# ESP32_ADC_DAC.net
KiCad netlist of a schematic drawn in Altium Designer
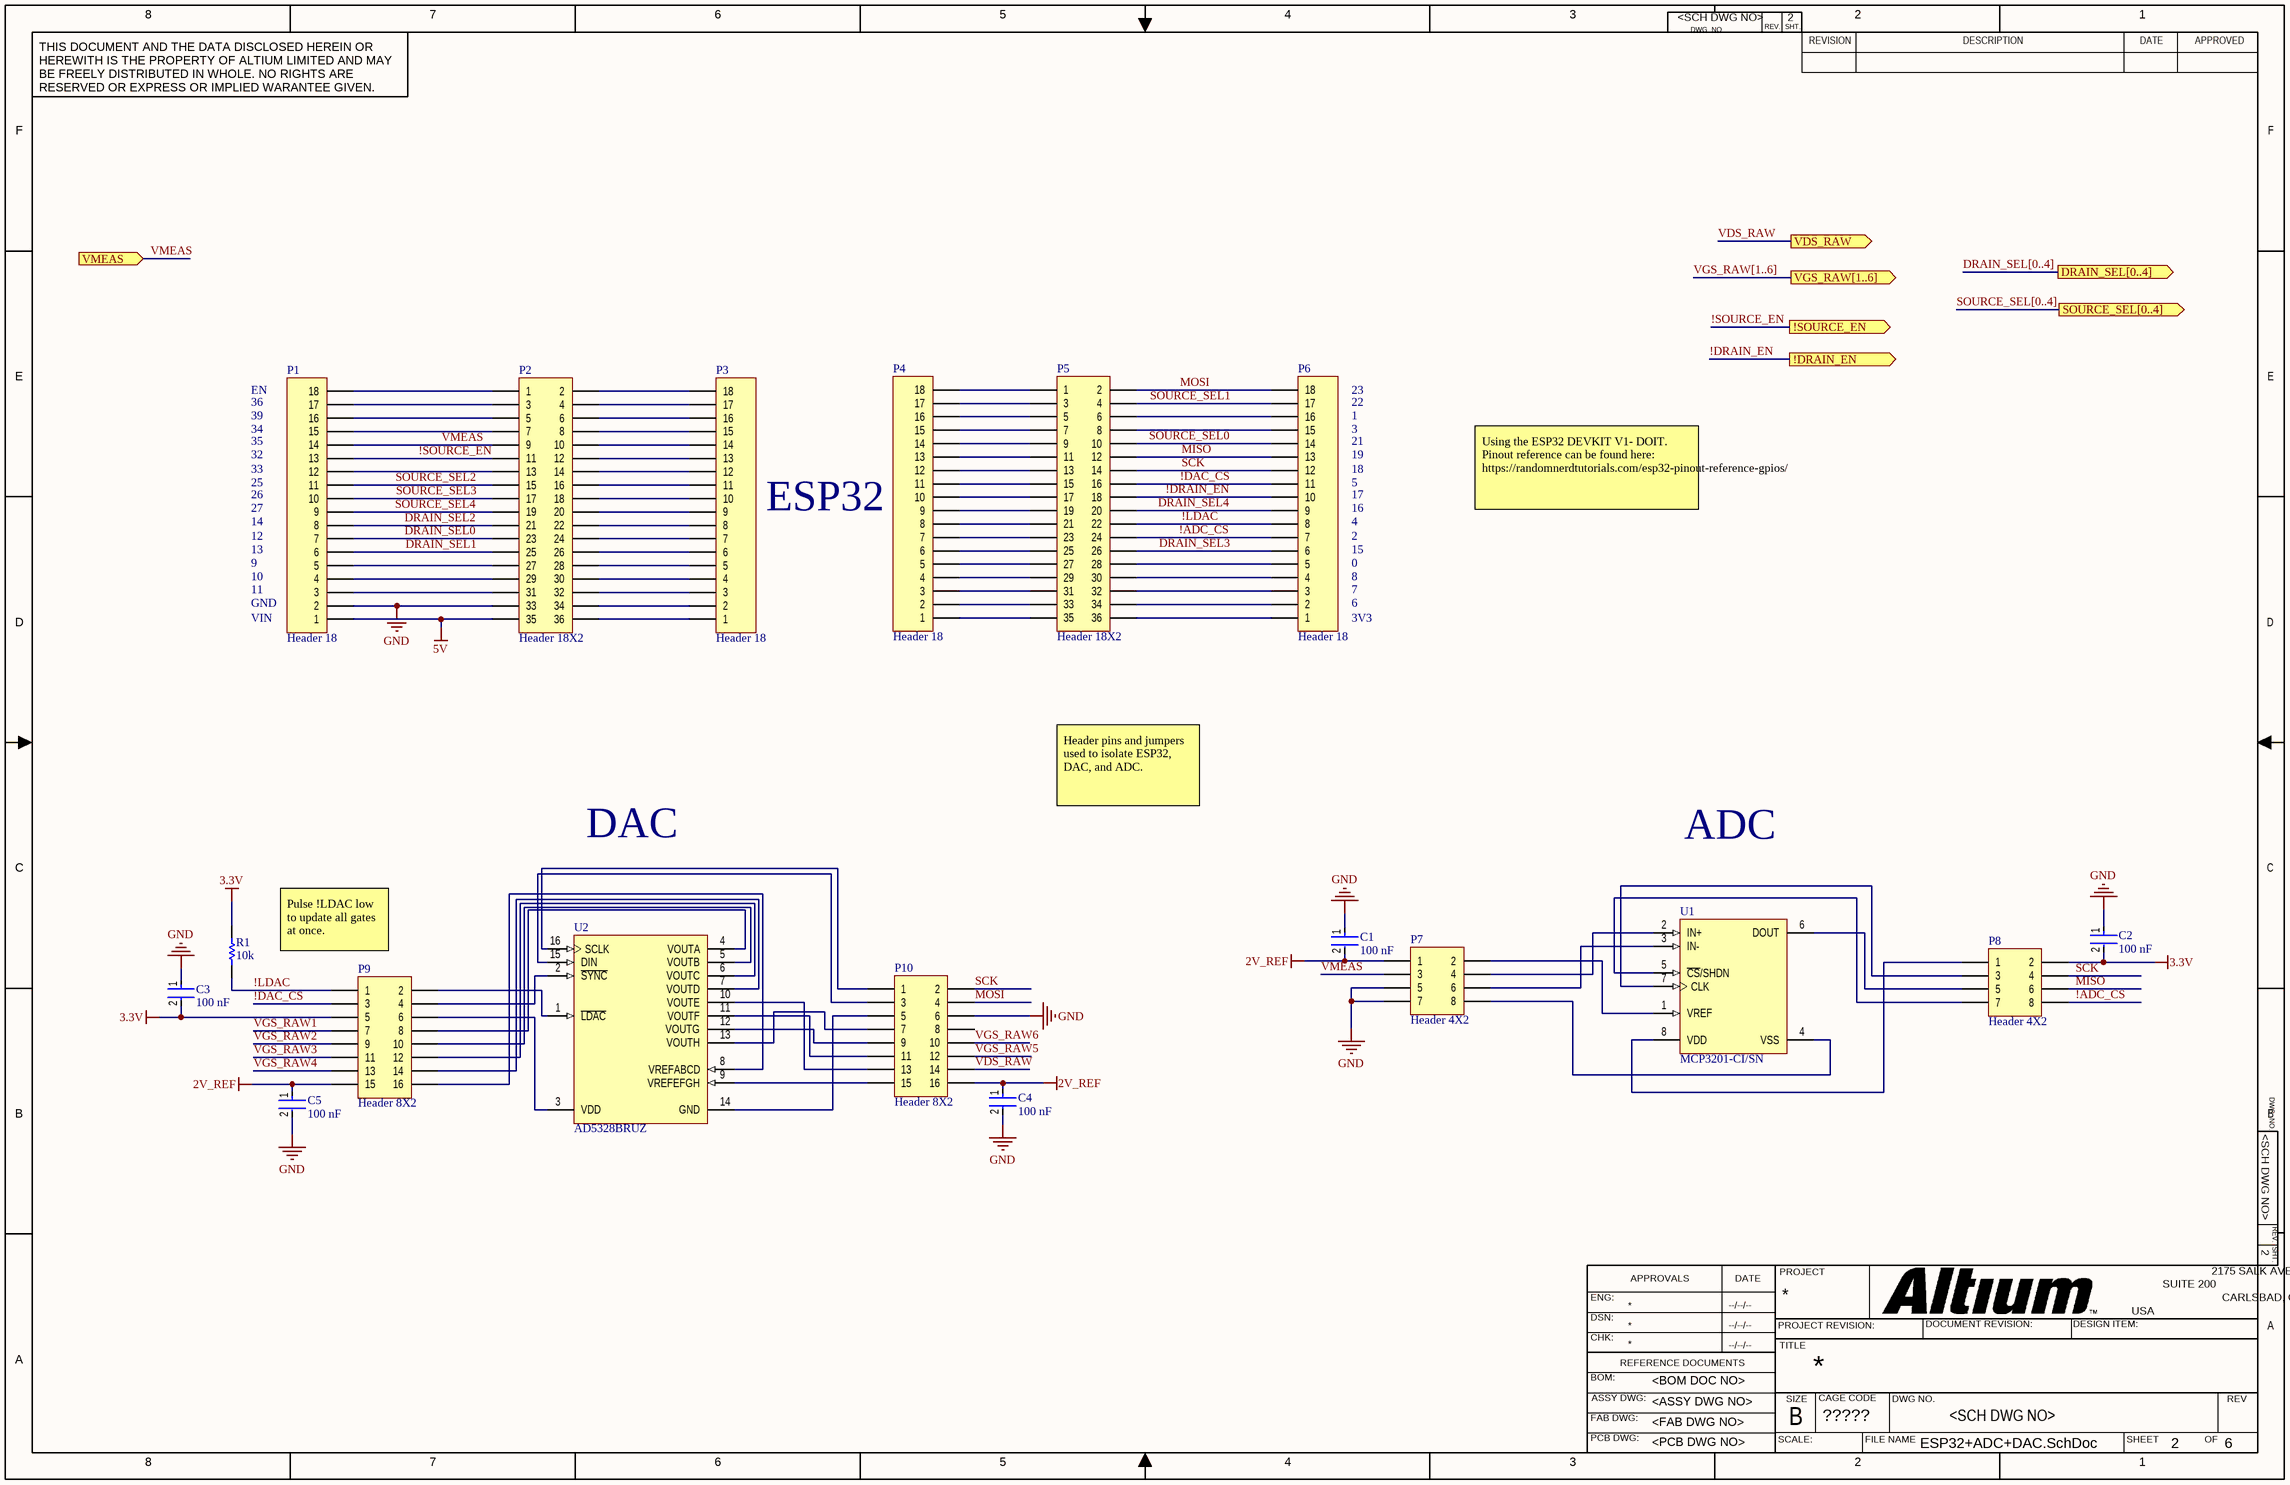
[diagram p0: ESP32+ADC+DAC.SchDoc]

(export (version "E")
  (design (tool "Eeschema 10.0.6"))
  (components
    (comp (ref "C1")
      (value "100 nF")
      (footprint "FP-C0805C-DN-MFG")
      (description "CAP CER 0.1UF 50V X7R 0805")
      (fields
        (field (name "MANUFACTURER PART NUMBER") "C0805C104K5RACTU")
        (field (name "MANUFACTURER") "KEMET")
      )
      (libsource (lib "Altium Content Vault") (part "b4654b650e69147ec39a6b967a45e02"))
    )
    (comp (ref "C2")
      (value "100 nF")
      (footprint "FP-C0805C-DN-MFG")
      (description "CAP CER 0.1UF 50V X7R 0805")
      (fields
        (field (name "MANUFACTURER PART NUMBER") "C0805C104K5RACTU")
        (field (name "MANUFACTURER") "KEMET")
      )
      (libsource (lib "Altium Content Vault") (part "b4654b650e69147ec39a6b967a45e02"))
    )
    (comp (ref "C3")
      (value "100 nF")
      (footprint "FP-C0805C-DN-MFG")
      (description "CAP CER 0.1UF 50V X7R 0805")
      (fields
        (field (name "MANUFACTURER PART NUMBER") "C0805C104K5RACTU")
        (field (name "MANUFACTURER") "KEMET")
      )
      (libsource (lib "Altium Content Vault") (part "b4654b650e69147ec39a6b967a45e02"))
    )
    (comp (ref "C4")
      (value "100 nF")
      (footprint "FP-C0805C-DN-MFG")
      (description "CAP CER 0.1UF 50V X7R 0805")
      (fields
        (field (name "MANUFACTURER PART NUMBER") "C0805C104K5RACTU")
        (field (name "MANUFACTURER") "KEMET")
      )
      (libsource (lib "Altium Content Vault") (part "b4654b650e69147ec39a6b967a45e02"))
    )
    (comp (ref "C5")
      (value "100 nF")
      (footprint "FP-C0805C-DN-MFG")
      (description "CAP CER 0.1UF 50V X7R 0805")
      (fields
        (field (name "MANUFACTURER PART NUMBER") "C0805C104K5RACTU")
        (field (name "MANUFACTURER") "KEMET")
      )
      (libsource (lib "Altium Content Vault") (part "b4654b650e69147ec39a6b967a45e02"))
    )
    (comp (ref "P1")
      (value "Header 18")
      (footprint "HDR1X18")
      (description "Header, 18-Pin")
      (fields (field (name "PUBLISHER") "Altium Limited"))
      (libsource (lib "Miscellaneous Connectors") (part "Header 18"))
    )
    (comp (ref "P2")
      (value "Header 18X2")
      (footprint "HDR2X18")
      (description "Header, 18-Pin, Dual row")
      (fields (field (name "PUBLISHER") "Altium Limited"))
      (libsource (lib "Miscellaneous Connectors") (part "Header 18X2"))
    )
    (comp (ref "P3")
      (value "Header 18")
      (footprint "HDR1X18")
      (description "Header, 18-Pin")
      (fields (field (name "PUBLISHER") "Altium Limited"))
      (libsource (lib "") (part "Header 18_1"))
    )
    (comp (ref "P4")
      (value "Header 18")
      (footprint "HDR1X18")
      (description "Header, 18-Pin")
      (fields (field (name "PUBLISHER") "Altium Limited"))
      (libsource (lib "Miscellaneous Connectors") (part "Header 18"))
    )
    (comp (ref "P5")
      (value "Header 18X2")
      (footprint "HDR2X18")
      (description "Header, 18-Pin, Dual row")
      (fields (field (name "PUBLISHER") "Altium Limited"))
      (libsource (lib "Miscellaneous Connectors") (part "Header 18X2"))
    )
    (comp (ref "P6")
      (value "Header 18")
      (footprint "HDR1X18")
      (description "Header, 18-Pin")
      (fields (field (name "PUBLISHER") "Altium Limited"))
      (libsource (lib "") (part "Header 18_1"))
    )
    (comp (ref "P7")
      (value "Header 4X2")
      (footprint "HDR2X4")
      (description "Header, 4-Pin, Dual row")
      (fields (field (name "PUBLISHER") "Altium Limited"))
      (libsource (lib "Miscellaneous Connectors") (part "Header 4X2"))
    )
    (comp (ref "P8")
      (value "Header 4X2")
      (footprint "HDR2X4")
      (description "Header, 4-Pin, Dual row")
      (fields (field (name "PUBLISHER") "Altium Limited"))
      (libsource (lib "Miscellaneous Connectors") (part "Header 4X2"))
    )
    (comp (ref "P9")
      (value "Header 8X2")
      (footprint "HDR2X8")
      (description "Header, 8-Pin, Dual row")
      (fields (field (name "PUBLISHER") "Altium Limited"))
      (libsource (lib "Miscellaneous Connectors") (part "Header 8X2"))
    )
    (comp (ref "P10")
      (value "Header 8X2")
      (footprint "HDR2X8")
      (description "Header, 8-Pin, Dual row")
      (fields (field (name "PUBLISHER") "Altium Limited"))
      (libsource (lib "Miscellaneous Connectors") (part "Header 8X2"))
    )
    (comp (ref "R1")
      (value "10k")
      (footprint "RESC2013X60X35NL10T20")
      (description "Chip Resistor, 10 KOhm, +/- 1%, 0.125 W, -55 to 155 degC, 0805 (2012 Metric), RoHS, Tape and Reel")
      (fields (field (name "MANUFACTURER") "Yageo"))
      (libsource (lib "Altium Content Vault") (part "RES-2"))
    )
    (comp (ref "U1")
      (value "MCP3201-CI/SN")
      (footprint "SOIC-SN8_L")
      (libsource (lib "Altium Content Vault") (part "CON-ADC-MCP3001-8"))
    )
    (comp (ref "U2")
      (value "AD5328BRUZ")
      (footprint "RU-16_L")
      (fields (field (name "GENERIC PART NUMBER") "AD5328") (field (name "MANUFACTURER") "Analog Devices"))
      (libsource (lib "Altium Content Vault") (part "ADI-AD5328-RU-16"))
    )
  )
  (nets
    (net (code "1") (name "/!ADC_CS") (class "Default")
      (node (ref "P5") (pin "24") (pinfunction "24_24") (pintype "passive"))
      (node (ref "P6") (pin "7") (pinfunction "7_7") (pintype "passive"))
      (node (ref "P8") (pin "8") (pinfunction "8_8") (pintype "passive"))
    )
    (net (code "2") (name "/!DAC_CS") (class "Default")
      (node (ref "P5") (pin "16") (pinfunction "16_16") (pintype "passive"))
      (node (ref "P6") (pin "11") (pinfunction "11_11") (pintype "passive"))
      (node (ref "P9") (pin "3") (pinfunction "3_3") (pintype "passive"))
    )
    (net (code "3") (name "/!DRAIN_EN") (class "Default")
      (node (ref "P5") (pin "18") (pinfunction "18_18") (pintype "passive"))
      (node (ref "P6") (pin "10") (pinfunction "10_10") (pintype "passive"))
    )
    (net (code "4") (name "/!LDAC") (class "Default")
      (node (ref "P5") (pin "22") (pinfunction "22_22") (pintype "passive"))
      (node (ref "P6") (pin "8") (pinfunction "8_8") (pintype "passive"))
      (node (ref "P9") (pin "1") (pinfunction "1_1") (pintype "passive"))
      (node (ref "R1") (pin "1") (pinfunction "1_1") (pintype "passive"))
    )
    (net (code "5") (name "/!SOURCE_EN") (class "Default")
      (node (ref "P1") (pin "13") (pinfunction "13_13") (pintype "passive"))
      (node (ref "P2") (pin "11") (pinfunction "11_11") (pintype "passive"))
    )
    (net (code "6") (name "/DRAIN_SEL0") (class "Default")
      (node (ref "P1") (pin "7") (pinfunction "7_7") (pintype "passive"))
      (node (ref "P2") (pin "23") (pinfunction "23_23") (pintype "passive"))
    )
    (net (code "7") (name "/DRAIN_SEL1") (class "Default")
      (node (ref "P1") (pin "6") (pinfunction "6_6") (pintype "passive"))
      (node (ref "P2") (pin "25") (pinfunction "25_25") (pintype "passive"))
    )
    (net (code "8") (name "/DRAIN_SEL2") (class "Default")
      (node (ref "P1") (pin "8") (pinfunction "8_8") (pintype "passive"))
      (node (ref "P2") (pin "21") (pinfunction "21_21") (pintype "passive"))
    )
    (net (code "9") (name "/DRAIN_SEL3") (class "Default")
      (node (ref "P5") (pin "26") (pinfunction "26_26") (pintype "passive"))
      (node (ref "P6") (pin "6") (pinfunction "6_6") (pintype "passive"))
    )
    (net (code "10") (name "/DRAIN_SEL4") (class "Default")
      (node (ref "P5") (pin "20") (pinfunction "20_20") (pintype "passive"))
      (node (ref "P6") (pin "9") (pinfunction "9_9") (pintype "passive"))
    )
    (net (code "12") (name "/MISO") (class "Default")
      (node (ref "P5") (pin "12") (pinfunction "12_12") (pintype "passive"))
      (node (ref "P6") (pin "13") (pinfunction "13_13") (pintype "passive"))
      (node (ref "P8") (pin "6") (pinfunction "6_6") (pintype "passive"))
    )
    (net (code "13") (name "/MOSI") (class "Default")
      (node (ref "P10") (pin "4") (pinfunction "4_4") (pintype "passive"))
      (node (ref "P5") (pin "2") (pinfunction "2_2") (pintype "passive"))
      (node (ref "P6") (pin "18") (pinfunction "18_18") (pintype "passive"))
    )
    (net (code "14") (name "/SCK") (class "Default")
      (node (ref "P10") (pin "2") (pinfunction "2_2") (pintype "passive"))
      (node (ref "P5") (pin "14") (pinfunction "14_14") (pintype "passive"))
      (node (ref "P6") (pin "12") (pinfunction "12_12") (pintype "passive"))
      (node (ref "P8") (pin "4") (pinfunction "4_4") (pintype "passive"))
    )
    (net (code "15") (name "/SOURCE_SEL0") (class "Default")
      (node (ref "P5") (pin "10") (pinfunction "10_10") (pintype "passive"))
      (node (ref "P6") (pin "14") (pinfunction "14_14") (pintype "passive"))
    )
    (net (code "16") (name "/SOURCE_SEL1") (class "Default")
      (node (ref "P5") (pin "4") (pinfunction "4_4") (pintype "passive"))
      (node (ref "P6") (pin "17") (pinfunction "17_17") (pintype "passive"))
    )
    (net (code "17") (name "/SOURCE_SEL2") (class "Default")
      (node (ref "P1") (pin "11") (pinfunction "11_11") (pintype "passive"))
      (node (ref "P2") (pin "15") (pinfunction "15_15") (pintype "passive"))
    )
    (net (code "18") (name "/SOURCE_SEL3") (class "Default")
      (node (ref "P1") (pin "10") (pinfunction "10_10") (pintype "passive"))
      (node (ref "P2") (pin "17") (pinfunction "17_17") (pintype "passive"))
    )
    (net (code "19") (name "/SOURCE_SEL4") (class "Default")
      (node (ref "P1") (pin "9") (pinfunction "9_9") (pintype "passive"))
      (node (ref "P2") (pin "19") (pinfunction "19_19") (pintype "passive"))
    )
    (net (code "21") (name "/VDS_RAW") (class "Default")
      (node (ref "P10") (pin "14") (pinfunction "14_14") (pintype "passive"))
    )
    (net (code "22") (name "/VGS_RAW1") (class "Default")
      (node (ref "P9") (pin "7") (pinfunction "7_7") (pintype "passive"))
    )
    (net (code "23") (name "/VGS_RAW2") (class "Default")
      (node (ref "P9") (pin "9") (pinfunction "9_9") (pintype "passive"))
    )
    (net (code "24") (name "/VGS_RAW3") (class "Default")
      (node (ref "P9") (pin "11") (pinfunction "11_11") (pintype "passive"))
    )
    (net (code "25") (name "/VGS_RAW4") (class "Default")
      (node (ref "P9") (pin "13") (pinfunction "13_13") (pintype "passive"))
    )
    (net (code "26") (name "/VGS_RAW5") (class "Default")
      (node (ref "P10") (pin "12") (pinfunction "12_12") (pintype "passive"))
    )
    (net (code "27") (name "/VGS_RAW6") (class "Default")
      (node (ref "P10") (pin "10") (pinfunction "10_10") (pintype "passive"))
    )
    (net (code "29") (name "/VMEAS") (class "Default")
      (node (ref "P1") (pin "14") (pinfunction "14_14") (pintype "passive"))
      (node (ref "P2") (pin "9") (pinfunction "9_9") (pintype "passive"))
      (node (ref "P7") (pin "3") (pinfunction "3_3") (pintype "passive"))
    )
    (net (code "30") (name "2V_REF") (class "Default")
      (node (ref "C1") (pin "2") (pinfunction "2_2") (pintype "passive"))
      (node (ref "C4") (pin "1") (pinfunction "1_1") (pintype "passive"))
      (node (ref "C5") (pin "1") (pinfunction "1_1") (pintype "passive"))
      (node (ref "P10") (pin "16") (pinfunction "16_16") (pintype "passive"))
      (node (ref "P7") (pin "1") (pinfunction "1_1") (pintype "passive"))
      (node (ref "P9") (pin "15") (pinfunction "15_15") (pintype "passive"))
    )
    (net (code "31") (name "3.3V") (class "Default")
      (node (ref "C2") (pin "2") (pinfunction "2_2") (pintype "passive"))
      (node (ref "C3") (pin "2") (pinfunction "2_2") (pintype "passive"))
      (node (ref "P8") (pin "2") (pinfunction "2_2") (pintype "passive"))
      (node (ref "P9") (pin "5") (pinfunction "5_5") (pintype "passive"))
      (node (ref "R1") (pin "2") (pinfunction "2_2") (pintype "passive"))
    )
    (net (code "32") (name "5V") (class "Default")
      (node (ref "P1") (pin "1") (pinfunction "1_1") (pintype "passive"))
      (node (ref "P2") (pin "35") (pinfunction "35_35") (pintype "passive"))
    )
    (net (code "33") (name "GND") (class "Default")
      (node (ref "C1") (pin "1") (pinfunction "1_1") (pintype "passive"))
      (node (ref "C2") (pin "1") (pinfunction "1_1") (pintype "passive"))
      (node (ref "C3") (pin "1") (pinfunction "1_1") (pintype "passive"))
      (node (ref "C4") (pin "2") (pinfunction "2_2") (pintype "passive"))
      (node (ref "C5") (pin "2") (pinfunction "2_2") (pintype "passive"))
      (node (ref "P1") (pin "2") (pinfunction "2_2") (pintype "passive"))
      (node (ref "P10") (pin "6") (pinfunction "6_6") (pintype "passive"))
      (node (ref "P2") (pin "33") (pinfunction "33_33") (pintype "passive"))
      (node (ref "P7") (pin "5") (pinfunction "5_5") (pintype "passive"))
      (node (ref "P7") (pin "7") (pinfunction "7_7") (pintype "passive"))
    )
    (net (code "34") (name "Net-(P1-Pad3)") (class "Default")
      (node (ref "P1") (pin "3") (pinfunction "3_3") (pintype "passive"))
      (node (ref "P2") (pin "31") (pinfunction "31_31") (pintype "passive"))
    )
    (net (code "35") (name "Net-(P1-Pad4)") (class "Default")
      (node (ref "P1") (pin "4") (pinfunction "4_4") (pintype "passive"))
      (node (ref "P2") (pin "29") (pinfunction "29_29") (pintype "passive"))
    )
    (net (code "36") (name "Net-(P1-Pad5)") (class "Default")
      (node (ref "P1") (pin "5") (pinfunction "5_5") (pintype "passive"))
      (node (ref "P2") (pin "27") (pinfunction "27_27") (pintype "passive"))
    )
    (net (code "37") (name "Net-(P1-Pad12)") (class "Default")
      (node (ref "P1") (pin "12") (pinfunction "12_12") (pintype "passive"))
      (node (ref "P2") (pin "13") (pinfunction "13_13") (pintype "passive"))
    )
    (net (code "38") (name "Net-(P1-Pad15)") (class "Default")
      (node (ref "P1") (pin "15") (pinfunction "15_15") (pintype "passive"))
      (node (ref "P2") (pin "7") (pinfunction "7_7") (pintype "passive"))
    )
    (net (code "39") (name "Net-(P1-Pad16)") (class "Default")
      (node (ref "P1") (pin "16") (pinfunction "16_16") (pintype "passive"))
      (node (ref "P2") (pin "5") (pinfunction "5_5") (pintype "passive"))
    )
    (net (code "40") (name "Net-(P1-Pad17)") (class "Default")
      (node (ref "P1") (pin "17") (pinfunction "17_17") (pintype "passive"))
      (node (ref "P2") (pin "3") (pinfunction "3_3") (pintype "passive"))
    )
    (net (code "41") (name "Net-(P1-Pad18)") (class "Default")
      (node (ref "P1") (pin "18") (pinfunction "18_18") (pintype "passive"))
      (node (ref "P2") (pin "1") (pinfunction "1_1") (pintype "passive"))
    )
    (net (code "42") (name "Net-(P2-Pad2)") (class "Default")
      (node (ref "P2") (pin "2") (pinfunction "2_2") (pintype "passive"))
      (node (ref "P3") (pin "18") (pinfunction "18_18") (pintype "passive"))
    )
    (net (code "43") (name "Net-(P2-Pad4)") (class "Default")
      (node (ref "P2") (pin "4") (pinfunction "4_4") (pintype "passive"))
      (node (ref "P3") (pin "17") (pinfunction "17_17") (pintype "passive"))
    )
    (net (code "44") (name "Net-(P2-Pad6)") (class "Default")
      (node (ref "P2") (pin "6") (pinfunction "6_6") (pintype "passive"))
      (node (ref "P3") (pin "16") (pinfunction "16_16") (pintype "passive"))
    )
    (net (code "45") (name "Net-(P2-Pad8)") (class "Default")
      (node (ref "P2") (pin "8") (pinfunction "8_8") (pintype "passive"))
      (node (ref "P3") (pin "15") (pinfunction "15_15") (pintype "passive"))
    )
    (net (code "46") (name "Net-(P2-Pad10)") (class "Default")
      (node (ref "P2") (pin "10") (pinfunction "10_10") (pintype "passive"))
      (node (ref "P3") (pin "14") (pinfunction "14_14") (pintype "passive"))
    )
    (net (code "47") (name "Net-(P2-Pad12)") (class "Default")
      (node (ref "P2") (pin "12") (pinfunction "12_12") (pintype "passive"))
      (node (ref "P3") (pin "13") (pinfunction "13_13") (pintype "passive"))
    )
    (net (code "48") (name "Net-(P2-Pad14)") (class "Default")
      (node (ref "P2") (pin "14") (pinfunction "14_14") (pintype "passive"))
      (node (ref "P3") (pin "12") (pinfunction "12_12") (pintype "passive"))
    )
    (net (code "49") (name "Net-(P2-Pad16)") (class "Default")
      (node (ref "P2") (pin "16") (pinfunction "16_16") (pintype "passive"))
      (node (ref "P3") (pin "11") (pinfunction "11_11") (pintype "passive"))
    )
    (net (code "50") (name "Net-(P2-Pad18)") (class "Default")
      (node (ref "P2") (pin "18") (pinfunction "18_18") (pintype "passive"))
      (node (ref "P3") (pin "10") (pinfunction "10_10") (pintype "passive"))
    )
    (net (code "51") (name "Net-(P2-Pad20)") (class "Default")
      (node (ref "P2") (pin "20") (pinfunction "20_20") (pintype "passive"))
      (node (ref "P3") (pin "9") (pinfunction "9_9") (pintype "passive"))
    )
    (net (code "52") (name "Net-(P2-Pad22)") (class "Default")
      (node (ref "P2") (pin "22") (pinfunction "22_22") (pintype "passive"))
      (node (ref "P3") (pin "8") (pinfunction "8_8") (pintype "passive"))
    )
    (net (code "53") (name "Net-(P2-Pad24)") (class "Default")
      (node (ref "P2") (pin "24") (pinfunction "24_24") (pintype "passive"))
      (node (ref "P3") (pin "7") (pinfunction "7_7") (pintype "passive"))
    )
    (net (code "54") (name "Net-(P2-Pad26)") (class "Default")
      (node (ref "P2") (pin "26") (pinfunction "26_26") (pintype "passive"))
      (node (ref "P3") (pin "6") (pinfunction "6_6") (pintype "passive"))
    )
    (net (code "55") (name "Net-(P2-Pad28)") (class "Default")
      (node (ref "P2") (pin "28") (pinfunction "28_28") (pintype "passive"))
      (node (ref "P3") (pin "5") (pinfunction "5_5") (pintype "passive"))
    )
    (net (code "56") (name "Net-(P2-Pad30)") (class "Default")
      (node (ref "P2") (pin "30") (pinfunction "30_30") (pintype "passive"))
      (node (ref "P3") (pin "4") (pinfunction "4_4") (pintype "passive"))
    )
    (net (code "57") (name "Net-(P2-Pad32)") (class "Default")
      (node (ref "P2") (pin "32") (pinfunction "32_32") (pintype "passive"))
      (node (ref "P3") (pin "3") (pinfunction "3_3") (pintype "passive"))
    )
    (net (code "58") (name "Net-(P2-Pad34)") (class "Default")
      (node (ref "P2") (pin "34") (pinfunction "34_34") (pintype "passive"))
      (node (ref "P3") (pin "2") (pinfunction "2_2") (pintype "passive"))
    )
    (net (code "59") (name "Net-(P2-Pad36)") (class "Default")
      (node (ref "P2") (pin "36") (pinfunction "36_36") (pintype "passive"))
      (node (ref "P3") (pin "1") (pinfunction "1_1") (pintype "passive"))
    )
    (net (code "60") (name "Net-(P4-Pad1)") (class "Default")
      (node (ref "P4") (pin "1") (pinfunction "1_1") (pintype "passive"))
      (node (ref "P5") (pin "35") (pinfunction "35_35") (pintype "passive"))
    )
    (net (code "61") (name "Net-(P4-Pad2)") (class "Default")
      (node (ref "P4") (pin "2") (pinfunction "2_2") (pintype "passive"))
      (node (ref "P5") (pin "33") (pinfunction "33_33") (pintype "passive"))
    )
    (net (code "62") (name "Net-(P4-Pad3)") (class "Default")
      (node (ref "P4") (pin "3") (pinfunction "3_3") (pintype "passive"))
      (node (ref "P5") (pin "31") (pinfunction "31_31") (pintype "passive"))
    )
    (net (code "63") (name "Net-(P4-Pad4)") (class "Default")
      (node (ref "P4") (pin "4") (pinfunction "4_4") (pintype "passive"))
      (node (ref "P5") (pin "29") (pinfunction "29_29") (pintype "passive"))
    )
    (net (code "64") (name "Net-(P4-Pad5)") (class "Default")
      (node (ref "P4") (pin "5") (pinfunction "5_5") (pintype "passive"))
      (node (ref "P5") (pin "27") (pinfunction "27_27") (pintype "passive"))
    )
    (net (code "65") (name "Net-(P4-Pad6)") (class "Default")
      (node (ref "P4") (pin "6") (pinfunction "6_6") (pintype "passive"))
      (node (ref "P5") (pin "25") (pinfunction "25_25") (pintype "passive"))
    )
    (net (code "66") (name "Net-(P4-Pad7)") (class "Default")
      (node (ref "P4") (pin "7") (pinfunction "7_7") (pintype "passive"))
      (node (ref "P5") (pin "23") (pinfunction "23_23") (pintype "passive"))
    )
    (net (code "67") (name "Net-(P4-Pad8)") (class "Default")
      (node (ref "P4") (pin "8") (pinfunction "8_8") (pintype "passive"))
      (node (ref "P5") (pin "21") (pinfunction "21_21") (pintype "passive"))
    )
    (net (code "68") (name "Net-(P4-Pad9)") (class "Default")
      (node (ref "P4") (pin "9") (pinfunction "9_9") (pintype "passive"))
      (node (ref "P5") (pin "19") (pinfunction "19_19") (pintype "passive"))
    )
    (net (code "69") (name "Net-(P4-Pad10)") (class "Default")
      (node (ref "P4") (pin "10") (pinfunction "10_10") (pintype "passive"))
      (node (ref "P5") (pin "17") (pinfunction "17_17") (pintype "passive"))
    )
    (net (code "70") (name "Net-(P4-Pad11)") (class "Default")
      (node (ref "P4") (pin "11") (pinfunction "11_11") (pintype "passive"))
      (node (ref "P5") (pin "15") (pinfunction "15_15") (pintype "passive"))
    )
    (net (code "71") (name "Net-(P4-Pad12)") (class "Default")
      (node (ref "P4") (pin "12") (pinfunction "12_12") (pintype "passive"))
      (node (ref "P5") (pin "13") (pinfunction "13_13") (pintype "passive"))
    )
    (net (code "72") (name "Net-(P4-Pad13)") (class "Default")
      (node (ref "P4") (pin "13") (pinfunction "13_13") (pintype "passive"))
      (node (ref "P5") (pin "11") (pinfunction "11_11") (pintype "passive"))
    )
    (net (code "73") (name "Net-(P4-Pad14)") (class "Default")
      (node (ref "P4") (pin "14") (pinfunction "14_14") (pintype "passive"))
      (node (ref "P5") (pin "9") (pinfunction "9_9") (pintype "passive"))
    )
    (net (code "74") (name "Net-(P4-Pad15)") (class "Default")
      (node (ref "P4") (pin "15") (pinfunction "15_15") (pintype "passive"))
      (node (ref "P5") (pin "7") (pinfunction "7_7") (pintype "passive"))
    )
    (net (code "75") (name "Net-(P4-Pad16)") (class "Default")
      (node (ref "P4") (pin "16") (pinfunction "16_16") (pintype "passive"))
      (node (ref "P5") (pin "5") (pinfunction "5_5") (pintype "passive"))
    )
    (net (code "76") (name "Net-(P4-Pad17)") (class "Default")
      (node (ref "P4") (pin "17") (pinfunction "17_17") (pintype "passive"))
      (node (ref "P5") (pin "3") (pinfunction "3_3") (pintype "passive"))
    )
    (net (code "77") (name "Net-(P4-Pad18)") (class "Default")
      (node (ref "P4") (pin "18") (pinfunction "18_18") (pintype "passive"))
      (node (ref "P5") (pin "1") (pinfunction "1_1") (pintype "passive"))
    )
    (net (code "78") (name "Net-(P5-Pad6)") (class "Default")
      (node (ref "P5") (pin "6") (pinfunction "6_6") (pintype "passive"))
      (node (ref "P6") (pin "16") (pinfunction "16_16") (pintype "passive"))
    )
    (net (code "79") (name "Net-(P5-Pad8)") (class "Default")
      (node (ref "P5") (pin "8") (pinfunction "8_8") (pintype "passive"))
      (node (ref "P6") (pin "15") (pinfunction "15_15") (pintype "passive"))
    )
    (net (code "80") (name "Net-(P5-Pad28)") (class "Default")
      (node (ref "P5") (pin "28") (pinfunction "28_28") (pintype "passive"))
      (node (ref "P6") (pin "5") (pinfunction "5_5") (pintype "passive"))
    )
    (net (code "81") (name "Net-(P5-Pad30)") (class "Default")
      (node (ref "P5") (pin "30") (pinfunction "30_30") (pintype "passive"))
      (node (ref "P6") (pin "4") (pinfunction "4_4") (pintype "passive"))
    )
    (net (code "82") (name "Net-(P5-Pad32)") (class "Default")
      (node (ref "P5") (pin "32") (pinfunction "32_32") (pintype "passive"))
      (node (ref "P6") (pin "3") (pinfunction "3_3") (pintype "passive"))
    )
    (net (code "83") (name "Net-(P5-Pad34)") (class "Default")
      (node (ref "P5") (pin "34") (pinfunction "34_34") (pintype "passive"))
      (node (ref "P6") (pin "2") (pinfunction "2_2") (pintype "passive"))
    )
    (net (code "84") (name "Net-(P5-Pad36)") (class "Default")
      (node (ref "P5") (pin "36") (pinfunction "36_36") (pintype "passive"))
      (node (ref "P6") (pin "1") (pinfunction "1_1") (pintype "passive"))
    )
    (net (code "85") (name "Net-(U1-CLK)") (class "Default")
      (node (ref "P8") (pin "3") (pinfunction "3_3") (pintype "passive"))
      (node (ref "U1") (pin "7") (pinfunction "CLK_7") (pintype "input"))
    )
    (net (code "86") (name "Net-(U1-DOUT)") (class "Default")
      (node (ref "P8") (pin "5") (pinfunction "5_5") (pintype "passive"))
      (node (ref "U1") (pin "6") (pinfunction "DOUT_6") (pintype "tri_state"))
    )
    (net (code "87") (name "Net-(U1-IN+)") (class "Default")
      (node (ref "P7") (pin "4") (pinfunction "4_4") (pintype "passive"))
      (node (ref "U1") (pin "2") (pinfunction "IN+_2") (pintype "input"))
    )
    (net (code "88") (name "Net-(U1-IN-)") (class "Default")
      (node (ref "P7") (pin "6") (pinfunction "6_6") (pintype "passive"))
      (node (ref "U1") (pin "3") (pinfunction "IN-_3") (pintype "input"))
    )
    (net (code "89") (name "Net-(U1-VDD)") (class "Default")
      (node (ref "P8") (pin "1") (pinfunction "1_1") (pintype "passive"))
      (node (ref "U1") (pin "8") (pinfunction "VDD_8") (pintype "power_in"))
    )
    (net (code "90") (name "Net-(U1-VREF)") (class "Default")
      (node (ref "P7") (pin "2") (pinfunction "2_2") (pintype "passive"))
      (node (ref "U1") (pin "1") (pinfunction "VREF_1") (pintype "input"))
    )
    (net (code "91") (name "Net-(U1-VSS)") (class "Default")
      (node (ref "P7") (pin "8") (pinfunction "8_8") (pintype "passive"))
      (node (ref "U1") (pin "4") (pinfunction "VSS_4") (pintype "power_in"))
    )
    (net (code "92") (name "Net-(U1-~{CS}{slash}SHDN)") (class "Default")
      (node (ref "P8") (pin "7") (pinfunction "7_7") (pintype "passive"))
      (node (ref "U1") (pin "5") (pinfunction "~{CS}/SHDN_5") (pintype "input"))
    )
    (net (code "93") (name "Net-(U2-DIN)") (class "Default")
      (node (ref "P10") (pin "3") (pinfunction "3_3") (pintype "passive"))
      (node (ref "U2") (pin "15") (pinfunction "DIN_15") (pintype "input"))
    )
    (net (code "94") (name "Net-(U2-GND)") (class "Default")
      (node (ref "P10") (pin "5") (pinfunction "5_5") (pintype "passive"))
      (node (ref "U2") (pin "14") (pinfunction "GND_14") (pintype "power_in"))
    )
    (net (code "95") (name "Net-(U2-SCLK)") (class "Default")
      (node (ref "P10") (pin "1") (pinfunction "1_1") (pintype "passive"))
      (node (ref "U2") (pin "16") (pinfunction "SCLK_16") (pintype "input"))
    )
    (net (code "96") (name "Net-(U2-VDD)") (class "Default")
      (node (ref "P9") (pin "6") (pinfunction "6_6") (pintype "passive"))
      (node (ref "U2") (pin "3") (pinfunction "VDD_3") (pintype "power_in"))
    )
    (net (code "97") (name "Net-(U2-VOUTA)") (class "Default")
      (node (ref "P9") (pin "8") (pinfunction "8_8") (pintype "passive"))
      (node (ref "U2") (pin "4") (pinfunction "VOUTA_4") (pintype "tri_state"))
    )
    (net (code "98") (name "Net-(U2-VOUTB)") (class "Default")
      (node (ref "P9") (pin "10") (pinfunction "10_10") (pintype "passive"))
      (node (ref "U2") (pin "5") (pinfunction "VOUTB_5") (pintype "tri_state"))
    )
    (net (code "99") (name "Net-(U2-VOUTC)") (class "Default")
      (node (ref "P9") (pin "12") (pinfunction "12_12") (pintype "passive"))
      (node (ref "U2") (pin "6") (pinfunction "VOUTC_6") (pintype "tri_state"))
    )
    (net (code "100") (name "Net-(U2-VOUTD)") (class "Default")
      (node (ref "P9") (pin "14") (pinfunction "14_14") (pintype "passive"))
      (node (ref "U2") (pin "7") (pinfunction "VOUTD_7") (pintype "tri_state"))
    )
    (net (code "101") (name "Net-(U2-VOUTE)") (class "Default")
      (node (ref "P10") (pin "13") (pinfunction "13_13") (pintype "passive"))
      (node (ref "U2") (pin "10") (pinfunction "VOUTE_10") (pintype "tri_state"))
    )
    (net (code "102") (name "Net-(U2-VOUTF)") (class "Default")
      (node (ref "P10") (pin "11") (pinfunction "11_11") (pintype "passive"))
      (node (ref "U2") (pin "11") (pinfunction "VOUTF_11") (pintype "tri_state"))
    )
    (net (code "103") (name "Net-(U2-VOUTG)") (class "Default")
      (node (ref "P10") (pin "9") (pinfunction "9_9") (pintype "passive"))
      (node (ref "U2") (pin "12") (pinfunction "VOUTG_12") (pintype "tri_state"))
    )
    (net (code "104") (name "Net-(U2-VOUTH)") (class "Default")
      (node (ref "P10") (pin "7") (pinfunction "7_7") (pintype "passive"))
      (node (ref "U2") (pin "13") (pinfunction "VOUTH_13") (pintype "tri_state"))
    )
    (net (code "105") (name "Net-(U2-VREFABCD)") (class "Default")
      (node (ref "P9") (pin "16") (pinfunction "16_16") (pintype "passive"))
      (node (ref "U2") (pin "8") (pinfunction "VREFABCD_8") (pintype "input"))
    )
    (net (code "106") (name "Net-(U2-VREFEFGH)") (class "Default")
      (node (ref "P10") (pin "15") (pinfunction "15_15") (pintype "passive"))
      (node (ref "U2") (pin "9") (pinfunction "VREFEFGH_9") (pintype "input"))
    )
    (net (code "107") (name "Net-(U2-~{LDAC})") (class "Default")
      (node (ref "P9") (pin "2") (pinfunction "2_2") (pintype "passive"))
      (node (ref "U2") (pin "1") (pinfunction "~{LDAC}_1") (pintype "input"))
    )
    (net (code "108") (name "Net-(U2-~{SYNC})") (class "Default")
      (node (ref "P9") (pin "4") (pinfunction "4_4") (pintype "passive"))
      (node (ref "U2") (pin "2") (pinfunction "~{SYNC}_2") (pintype "input"))
    )
    (net (code "109") (name "unconnected-(P10-Pad8)") (class "Default")
      (node (ref "P10") (pin "8") (pinfunction "8_8") (pintype "passive"))
    )
  )
)
